# EZEDA_OpenLightingController.net
KiCad netlist of a schematic drawn in EasyEDA Pro
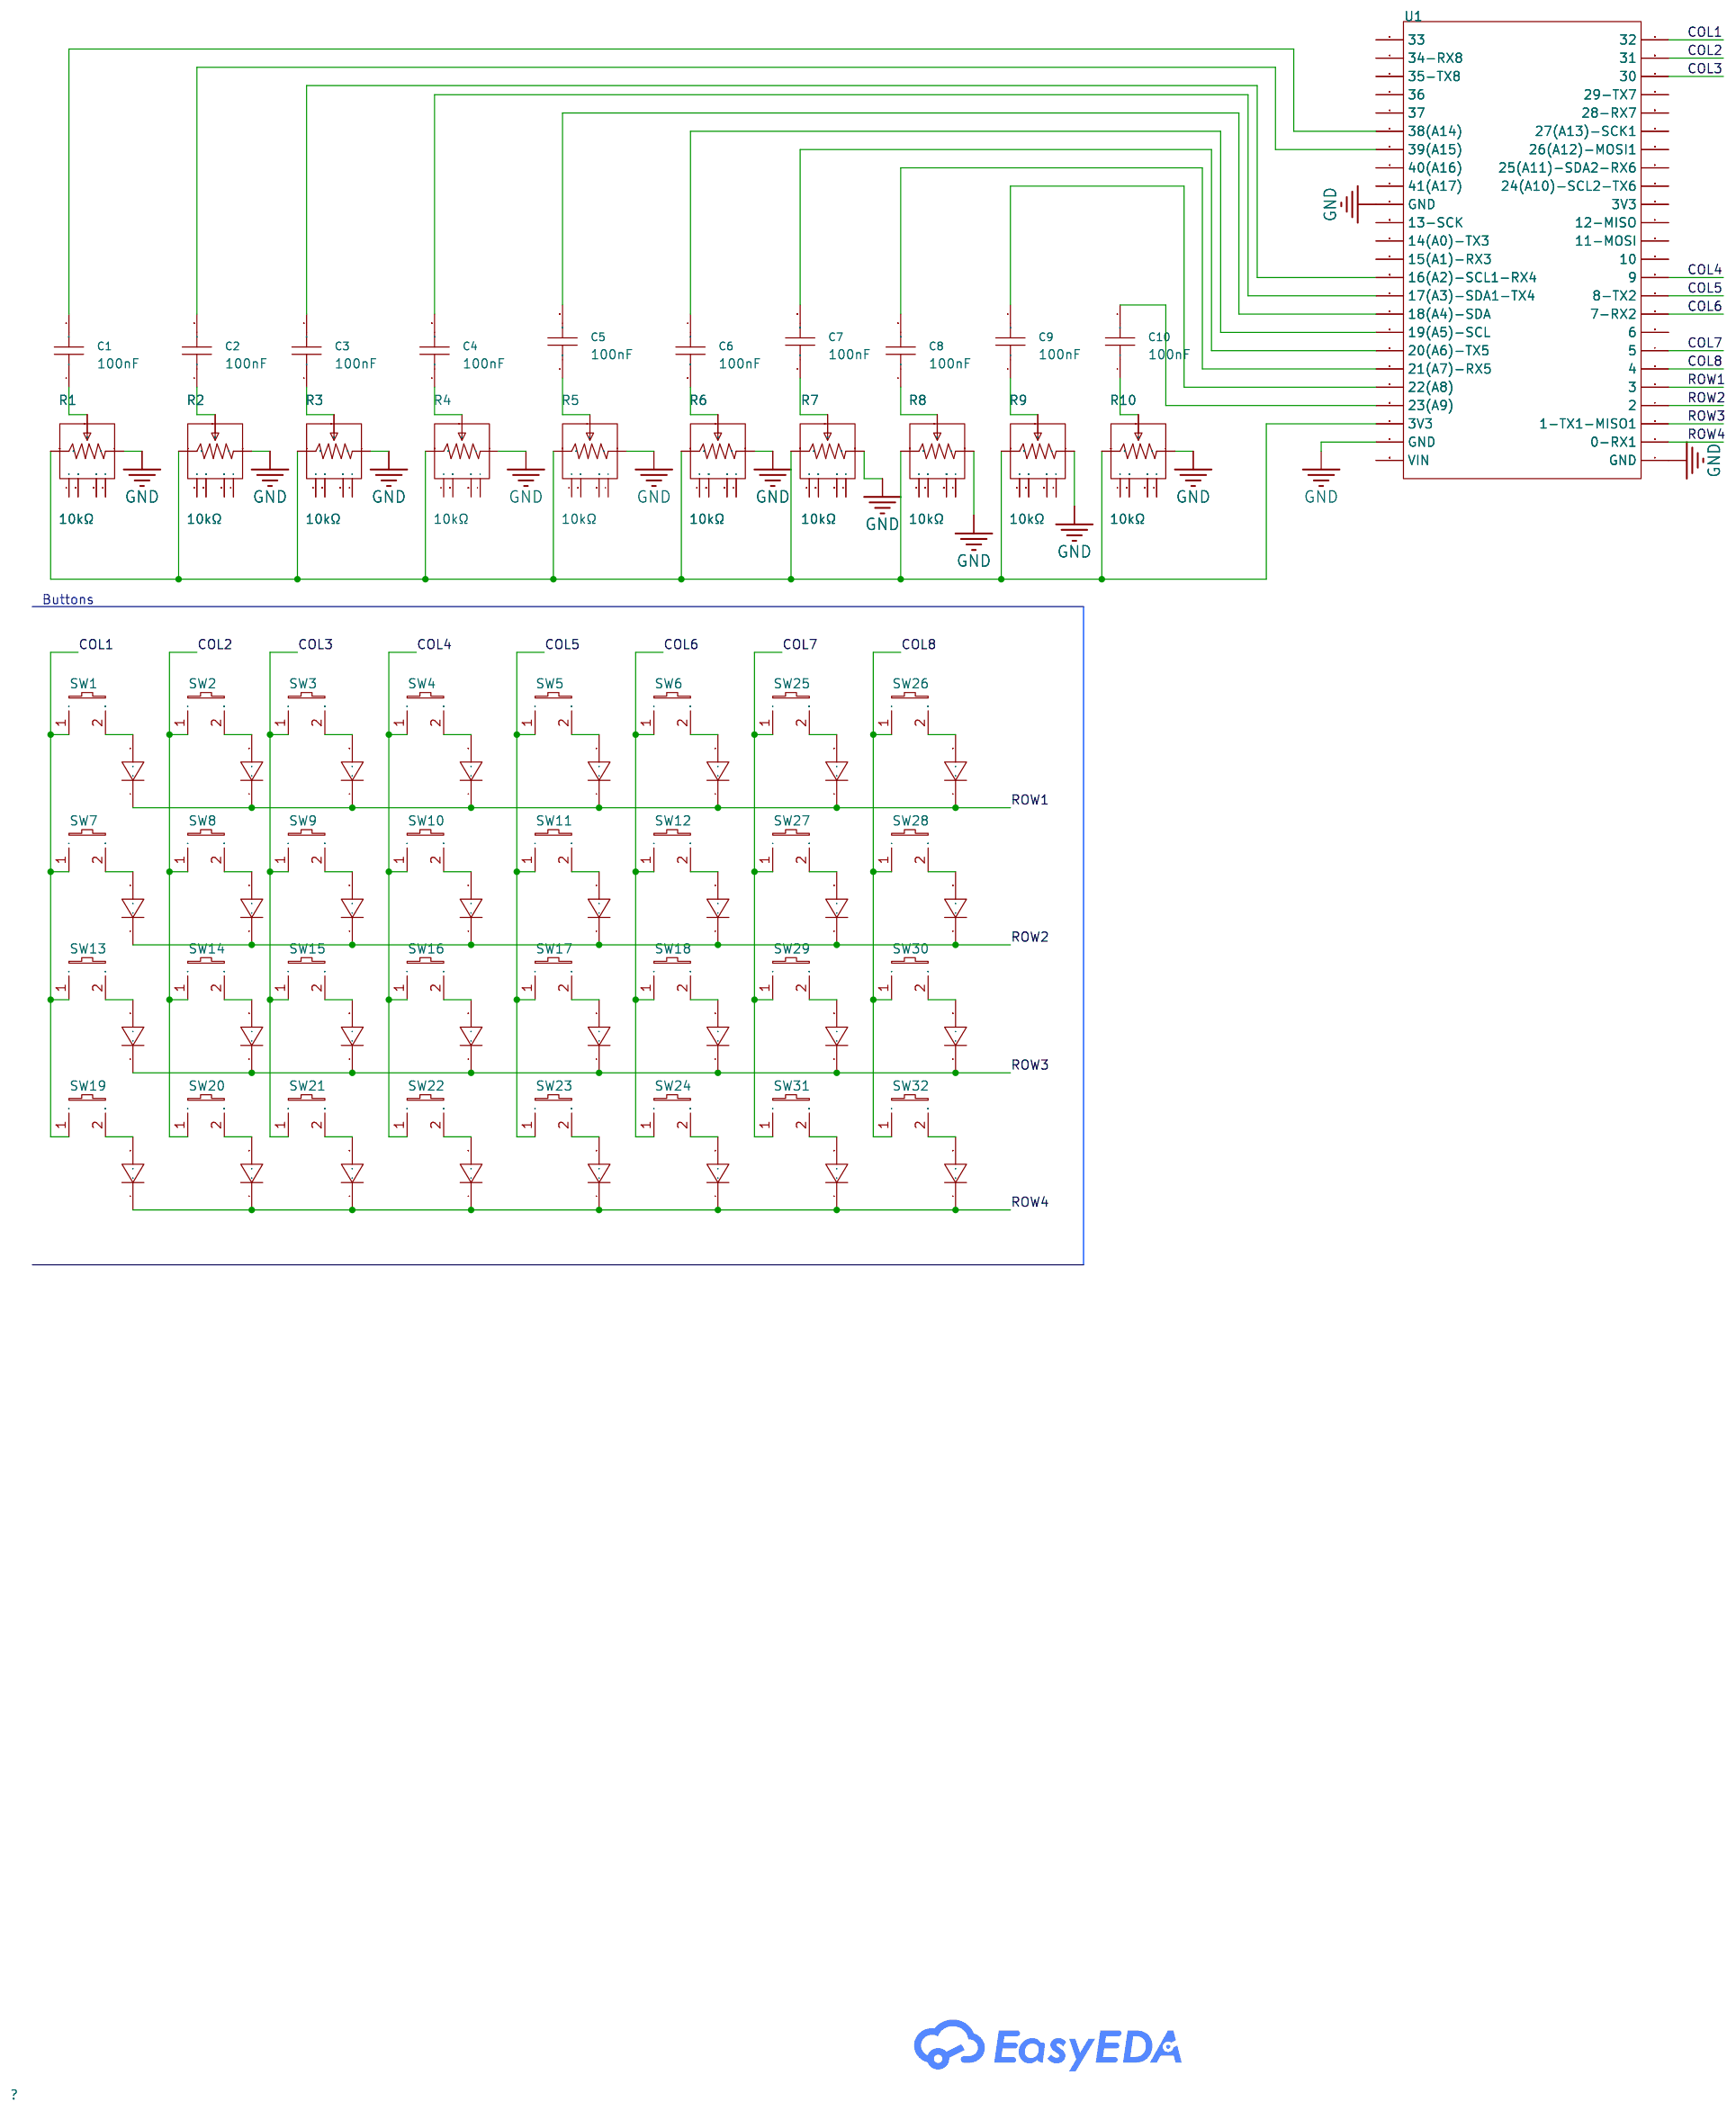
[diagram p0: schematic sheet]

(export (version "E")
  (design (tool "Eeschema 10.0.6"))
  (components
    (comp (ref "C1")
      (value "100nF")
      (footprint "easyedapro:C0603")
      (fields
        (field (name "Manufacturer Part") "CC1H104ZA1ED3F5P1100")
        (field (name "Manufacturer") "Dersonic(德尔创)")
      )
      (libsource (lib "easyedapro") (part "CL10B104KB8NNNC"))
    )
    (comp (ref "C2")
      (value "100nF")
      (footprint "easyedapro:C0603")
      (fields
        (field (name "Manufacturer Part") "CC1H104ZA1ED3F5P1100")
        (field (name "Manufacturer") "Dersonic(德尔创)")
      )
      (libsource (lib "easyedapro") (part "CL10B104KB8NNNC"))
    )
    (comp (ref "C3")
      (value "100nF")
      (footprint "easyedapro:C0603")
      (fields
        (field (name "Manufacturer Part") "CC1H104ZA1ED3F5P1100")
        (field (name "Manufacturer") "Dersonic(德尔创)")
      )
      (libsource (lib "easyedapro") (part "CL10B104KB8NNNC"))
    )
    (comp (ref "C4")
      (value "100nF")
      (footprint "easyedapro:C0603")
      (fields
        (field (name "Manufacturer Part") "CC1H104ZA1ED3F5P1100")
        (field (name "Manufacturer") "Dersonic(德尔创)")
      )
      (libsource (lib "easyedapro") (part "CL10B104KB8NNNC"))
    )
    (comp (ref "C5")
      (value "100nF")
      (footprint "easyedapro:C0603")
      (fields
        (field (name "Manufacturer Part") "CC1H104ZA1ED3F5P1100")
        (field (name "Manufacturer") "Dersonic(德尔创)")
      )
      (libsource (lib "easyedapro") (part "CL10B104KB8NNNC"))
    )
    (comp (ref "C6")
      (value "100nF")
      (footprint "easyedapro:C0603")
      (fields
        (field (name "Manufacturer Part") "CC1H104ZA1ED3F5P1100")
        (field (name "Manufacturer") "Dersonic(德尔创)")
      )
      (libsource (lib "easyedapro") (part "CL10B104KB8NNNC"))
    )
    (comp (ref "C7")
      (value "100nF")
      (footprint "easyedapro:C0603")
      (fields
        (field (name "Manufacturer Part") "CC1H104ZA1ED3F5P1100")
        (field (name "Manufacturer") "Dersonic(德尔创)")
      )
      (libsource (lib "easyedapro") (part "CL10B104KB8NNNC"))
    )
    (comp (ref "C8")
      (value "100nF")
      (footprint "easyedapro:C0603")
      (fields
        (field (name "Manufacturer Part") "CC1H104ZA1ED3F5P1100")
        (field (name "Manufacturer") "Dersonic(德尔创)")
      )
      (libsource (lib "easyedapro") (part "CL10B104KB8NNNC"))
    )
    (comp (ref "C9")
      (value "100nF")
      (footprint "easyedapro:C0603")
      (fields
        (field (name "Manufacturer Part") "CC1H104ZA1ED3F5P1100")
        (field (name "Manufacturer") "Dersonic(德尔创)")
      )
      (libsource (lib "easyedapro") (part "CL10B104KB8NNNC"))
    )
    (comp (ref "C10")
      (value "100nF")
      (footprint "easyedapro:C0603")
      (fields
        (field (name "Manufacturer Part") "CC1H104ZA1ED3F5P1100")
        (field (name "Manufacturer") "Dersonic(德尔创)")
      )
      (libsource (lib "easyedapro") (part "CL10B104KB8NNNC"))
    )
    (comp (ref "D1")
      (value "1N4148")
      (footprint "easyedapro:SOD-123F_L2.7-W1.6-LS3.8-RD")
      (fields (field (name "Manufacturer") "onsemi(安森美)"))
      (libsource (lib "easyedapro") (part "1N4148W_C81598"))
    )
    (comp (ref "D2")
      (value "1N4148")
      (footprint "easyedapro:SOD-123F_L2.7-W1.6-LS3.8-RD")
      (fields (field (name "Manufacturer") "onsemi(安森美)"))
      (libsource (lib "easyedapro") (part "1N4148W_C81598"))
    )
    (comp (ref "D3")
      (value "1N4148")
      (footprint "easyedapro:SOD-123F_L2.7-W1.6-LS3.8-RD")
      (fields (field (name "Manufacturer") "onsemi(安森美)"))
      (libsource (lib "easyedapro") (part "1N4148W_C81598"))
    )
    (comp (ref "D4")
      (value "1N4148")
      (footprint "easyedapro:SOD-123F_L2.7-W1.6-LS3.8-RD")
      (fields (field (name "Manufacturer") "onsemi(安森美)"))
      (libsource (lib "easyedapro") (part "1N4148W_C81598"))
    )
    (comp (ref "D5")
      (value "1N4148")
      (footprint "easyedapro:SOD-123F_L2.7-W1.6-LS3.8-RD")
      (fields (field (name "Manufacturer") "onsemi(安森美)"))
      (libsource (lib "easyedapro") (part "1N4148W_C81598"))
    )
    (comp (ref "D6")
      (value "1N4148")
      (footprint "easyedapro:SOD-123F_L2.7-W1.6-LS3.8-RD")
      (fields (field (name "Manufacturer") "onsemi(安森美)"))
      (libsource (lib "easyedapro") (part "1N4148W_C81598"))
    )
    (comp (ref "D7")
      (value "1N4148")
      (footprint "easyedapro:SOD-123F_L2.7-W1.6-LS3.8-RD")
      (fields (field (name "Manufacturer") "onsemi(安森美)"))
      (libsource (lib "easyedapro") (part "1N4148W_C81598"))
    )
    (comp (ref "D8")
      (value "1N4148")
      (footprint "easyedapro:SOD-123F_L2.7-W1.6-LS3.8-RD")
      (fields (field (name "Manufacturer") "onsemi(安森美)"))
      (libsource (lib "easyedapro") (part "1N4148W_C81598"))
    )
    (comp (ref "D9")
      (value "1N4148")
      (footprint "easyedapro:SOD-123F_L2.7-W1.6-LS3.8-RD")
      (fields (field (name "Manufacturer") "onsemi(安森美)"))
      (libsource (lib "easyedapro") (part "1N4148W_C81598"))
    )
    (comp (ref "D10")
      (value "1N4148")
      (footprint "easyedapro:SOD-123F_L2.7-W1.6-LS3.8-RD")
      (fields (field (name "Manufacturer") "onsemi(安森美)"))
      (libsource (lib "easyedapro") (part "1N4148W_C81598"))
    )
    (comp (ref "D11")
      (value "1N4148")
      (footprint "easyedapro:SOD-123F_L2.7-W1.6-LS3.8-RD")
      (fields (field (name "Manufacturer") "onsemi(安森美)"))
      (libsource (lib "easyedapro") (part "1N4148W_C81598"))
    )
    (comp (ref "D12")
      (value "1N4148")
      (footprint "easyedapro:SOD-123F_L2.7-W1.6-LS3.8-RD")
      (fields (field (name "Manufacturer") "onsemi(安森美)"))
      (libsource (lib "easyedapro") (part "1N4148W_C81598"))
    )
    (comp (ref "D13")
      (value "1N4148")
      (footprint "easyedapro:SOD-123F_L2.7-W1.6-LS3.8-RD")
      (fields (field (name "Manufacturer") "onsemi(安森美)"))
      (libsource (lib "easyedapro") (part "1N4148W_C81598"))
    )
    (comp (ref "D14")
      (value "1N4148")
      (footprint "easyedapro:SOD-123F_L2.7-W1.6-LS3.8-RD")
      (fields (field (name "Manufacturer") "onsemi(安森美)"))
      (libsource (lib "easyedapro") (part "1N4148W_C81598"))
    )
    (comp (ref "D15")
      (value "1N4148")
      (footprint "easyedapro:SOD-123F_L2.7-W1.6-LS3.8-RD")
      (fields (field (name "Manufacturer") "onsemi(安森美)"))
      (libsource (lib "easyedapro") (part "1N4148W_C81598"))
    )
    (comp (ref "D16")
      (value "1N4148")
      (footprint "easyedapro:SOD-123F_L2.7-W1.6-LS3.8-RD")
      (fields (field (name "Manufacturer") "onsemi(安森美)"))
      (libsource (lib "easyedapro") (part "1N4148W_C81598"))
    )
    (comp (ref "D17")
      (value "1N4148")
      (footprint "easyedapro:SOD-123F_L2.7-W1.6-LS3.8-RD")
      (fields (field (name "Manufacturer") "onsemi(安森美)"))
      (libsource (lib "easyedapro") (part "1N4148W_C81598"))
    )
    (comp (ref "D18")
      (value "1N4148")
      (footprint "easyedapro:SOD-123F_L2.7-W1.6-LS3.8-RD")
      (fields (field (name "Manufacturer") "onsemi(安森美)"))
      (libsource (lib "easyedapro") (part "1N4148W_C81598"))
    )
    (comp (ref "D19")
      (value "1N4148")
      (footprint "easyedapro:SOD-123F_L2.7-W1.6-LS3.8-RD")
      (fields (field (name "Manufacturer") "onsemi(安森美)"))
      (libsource (lib "easyedapro") (part "1N4148W_C81598"))
    )
    (comp (ref "D20")
      (value "1N4148")
      (footprint "easyedapro:SOD-123F_L2.7-W1.6-LS3.8-RD")
      (fields (field (name "Manufacturer") "onsemi(安森美)"))
      (libsource (lib "easyedapro") (part "1N4148W_C81598"))
    )
    (comp (ref "D21")
      (value "1N4148")
      (footprint "easyedapro:SOD-123F_L2.7-W1.6-LS3.8-RD")
      (fields (field (name "Manufacturer") "onsemi(安森美)"))
      (libsource (lib "easyedapro") (part "1N4148W_C81598"))
    )
    (comp (ref "D22")
      (value "1N4148")
      (footprint "easyedapro:SOD-123F_L2.7-W1.6-LS3.8-RD")
      (fields (field (name "Manufacturer") "onsemi(安森美)"))
      (libsource (lib "easyedapro") (part "1N4148W_C81598"))
    )
    (comp (ref "D23")
      (value "1N4148")
      (footprint "easyedapro:SOD-123F_L2.7-W1.6-LS3.8-RD")
      (fields (field (name "Manufacturer") "onsemi(安森美)"))
      (libsource (lib "easyedapro") (part "1N4148W_C81598"))
    )
    (comp (ref "D24")
      (value "1N4148")
      (footprint "easyedapro:SOD-123F_L2.7-W1.6-LS3.8-RD")
      (fields (field (name "Manufacturer") "onsemi(安森美)"))
      (libsource (lib "easyedapro") (part "1N4148W_C81598"))
    )
    (comp (ref "D25")
      (value "1N4148")
      (footprint "easyedapro:SOD-123F_L2.7-W1.6-LS3.8-RD")
      (fields (field (name "Manufacturer") "onsemi(安森美)"))
      (libsource (lib "easyedapro") (part "1N4148W_C81598"))
    )
    (comp (ref "D26")
      (value "1N4148")
      (footprint "easyedapro:SOD-123F_L2.7-W1.6-LS3.8-RD")
      (fields (field (name "Manufacturer") "onsemi(安森美)"))
      (libsource (lib "easyedapro") (part "1N4148W_C81598"))
    )
    (comp (ref "D27")
      (value "1N4148")
      (footprint "easyedapro:SOD-123F_L2.7-W1.6-LS3.8-RD")
      (fields (field (name "Manufacturer") "onsemi(安森美)"))
      (libsource (lib "easyedapro") (part "1N4148W_C81598"))
    )
    (comp (ref "D28")
      (value "1N4148")
      (footprint "easyedapro:SOD-123F_L2.7-W1.6-LS3.8-RD")
      (fields (field (name "Manufacturer") "onsemi(安森美)"))
      (libsource (lib "easyedapro") (part "1N4148W_C81598"))
    )
    (comp (ref "D29")
      (value "1N4148")
      (footprint "easyedapro:SOD-123F_L2.7-W1.6-LS3.8-RD")
      (fields (field (name "Manufacturer") "onsemi(安森美)"))
      (libsource (lib "easyedapro") (part "1N4148W_C81598"))
    )
    (comp (ref "D30")
      (value "1N4148")
      (footprint "easyedapro:SOD-123F_L2.7-W1.6-LS3.8-RD")
      (fields (field (name "Manufacturer") "onsemi(安森美)"))
      (libsource (lib "easyedapro") (part "1N4148W_C81598"))
    )
    (comp (ref "D31")
      (value "1N4148")
      (footprint "easyedapro:SOD-123F_L2.7-W1.6-LS3.8-RD")
      (fields (field (name "Manufacturer") "onsemi(安森美)"))
      (libsource (lib "easyedapro") (part "1N4148W_C81598"))
    )
    (comp (ref "D32")
      (value "1N4148")
      (footprint "easyedapro:SOD-123F_L2.7-W1.6-LS3.8-RD")
      (fields (field (name "Manufacturer") "onsemi(安森美)"))
      (libsource (lib "easyedapro") (part "1N4148W_C81598"))
    )
    (comp (ref "R1")
      (value "10kΩ")
      (footprint "easyedapro:RES-ADJ-TH_PTA6043-2015DPB103")
      (description "Resistance:10kΩ Tolerance:±20% Tolerance:±20% Voltage Rating:200V Power(Watts):250mW")
      (fields (field (name "Manufacturer Part") "PTA6043-2015CPB103") (field (name "Manufacturer") "BOURNS"))
      (libsource (lib "easyedapro") (part "PTA6043-2015CPB103"))
    )
    (comp (ref "R2")
      (value "10kΩ")
      (footprint "easyedapro:RES-ADJ-TH_PTA6043-2015DPB103")
      (description "Resistance:10kΩ Tolerance:±20% Tolerance:±20% Voltage Rating:200V Power(Watts):250mW")
      (fields (field (name "Manufacturer Part") "PTA6043-2015CPB103") (field (name "Manufacturer") "BOURNS"))
      (libsource (lib "easyedapro") (part "PTA6043-2015CPB103"))
    )
    (comp (ref "R3")
      (value "10kΩ")
      (footprint "easyedapro:RES-ADJ-TH_PTA6043-2015DPB103")
      (description "Resistance:10kΩ Tolerance:±20% Tolerance:±20% Voltage Rating:200V Power(Watts):250mW")
      (fields (field (name "Manufacturer Part") "PTA6043-2015CPB103") (field (name "Manufacturer") "BOURNS"))
      (libsource (lib "easyedapro") (part "PTA6043-2015CPB103"))
    )
    (comp (ref "R4")
      (value "10kΩ")
      (footprint "easyedapro:RES-ADJ-TH_PTA6043-2015DPB103")
      (description "Resistance:10kΩ Tolerance:±20% Tolerance:±20% Voltage Rating:200V Power(Watts):250mW")
      (fields (field (name "Manufacturer Part") "PTA6043-2015CPB103") (field (name "Manufacturer") "BOURNS"))
      (libsource (lib "easyedapro") (part "PTA6043-2015CPB103"))
    )
    (comp (ref "R5")
      (value "10kΩ")
      (footprint "easyedapro:RES-ADJ-TH_PTA6043-2015DPB103")
      (description "Resistance:10kΩ Tolerance:±20% Tolerance:±20% Voltage Rating:200V Power(Watts):250mW")
      (fields (field (name "Manufacturer Part") "PTA6043-2015CPB103") (field (name "Manufacturer") "BOURNS"))
      (libsource (lib "easyedapro") (part "PTA6043-2015CPB103"))
    )
    (comp (ref "R6")
      (value "10kΩ")
      (footprint "easyedapro:RES-ADJ-TH_PTA6043-2015DPB103")
      (description "Resistance:10kΩ Tolerance:±20% Tolerance:±20% Voltage Rating:200V Power(Watts):250mW")
      (fields (field (name "Manufacturer Part") "PTA6043-2015CPB103") (field (name "Manufacturer") "BOURNS"))
      (libsource (lib "easyedapro") (part "PTA6043-2015CPB103"))
    )
    (comp (ref "R7")
      (value "10kΩ")
      (footprint "easyedapro:RES-ADJ-TH_PTA6043-2015DPB103")
      (description "Resistance:10kΩ Tolerance:±20% Tolerance:±20% Voltage Rating:200V Power(Watts):250mW")
      (fields (field (name "Manufacturer Part") "PTA6043-2015CPB103") (field (name "Manufacturer") "BOURNS"))
      (libsource (lib "easyedapro") (part "PTA6043-2015CPB103"))
    )
    (comp (ref "R8")
      (value "10kΩ")
      (footprint "easyedapro:RES-ADJ-TH_PTA6043-2015DPB103")
      (description "Resistance:10kΩ Tolerance:±20% Tolerance:±20% Voltage Rating:200V Power(Watts):250mW")
      (fields (field (name "Manufacturer Part") "PTA6043-2015CPB103") (field (name "Manufacturer") "BOURNS"))
      (libsource (lib "easyedapro") (part "PTA6043-2015CPB103"))
    )
    (comp (ref "R9")
      (value "10kΩ")
      (footprint "easyedapro:RES-ADJ-TH_PTA6043-2015DPB103")
      (description "Resistance:10kΩ Tolerance:±20% Tolerance:±20% Voltage Rating:200V Power(Watts):250mW")
      (fields (field (name "Manufacturer Part") "PTA6043-2015CPB103") (field (name "Manufacturer") "BOURNS"))
      (libsource (lib "easyedapro") (part "PTA6043-2015CPB103"))
    )
    (comp (ref "R10")
      (value "10kΩ")
      (footprint "easyedapro:RES-ADJ-TH_PTA6043-2015DPB103")
      (description "Resistance:10kΩ Tolerance:±20% Tolerance:±20% Voltage Rating:200V Power(Watts):250mW")
      (fields (field (name "Manufacturer Part") "PTA6043-2015CPB103") (field (name "Manufacturer") "BOURNS"))
      (libsource (lib "easyedapro") (part "PTA6043-2015CPB103"))
    )
    (comp (ref "SW1")
      (value "MX Switch")
      (footprint "easyedapro:SW-TH_MX1A-11NW")
      (fields (field (name "Manufacturer Part") "MX1A-11NW") (field (name "Manufacturer") "CHERRY"))
      (libsource (lib "easyedapro") (part "MX1A-11NW"))
    )
    (comp (ref "SW2")
      (value "MX Switch")
      (footprint "easyedapro:SW-TH_MX1A-11NW")
      (fields (field (name "Manufacturer Part") "MX1A-11NW") (field (name "Manufacturer") "CHERRY"))
      (libsource (lib "easyedapro") (part "MX1A-11NW"))
    )
    (comp (ref "SW3")
      (value "MX Switch")
      (footprint "easyedapro:SW-TH_MX1A-11NW")
      (fields (field (name "Manufacturer Part") "MX1A-11NW") (field (name "Manufacturer") "CHERRY"))
      (libsource (lib "easyedapro") (part "MX1A-11NW"))
    )
    (comp (ref "SW4")
      (value "MX Switch")
      (footprint "easyedapro:SW-TH_MX1A-11NW")
      (fields (field (name "Manufacturer Part") "MX1A-11NW") (field (name "Manufacturer") "CHERRY"))
      (libsource (lib "easyedapro") (part "MX1A-11NW"))
    )
    (comp (ref "SW5")
      (value "MX Switch")
      (footprint "easyedapro:SW-TH_MX1A-11NW")
      (fields (field (name "Manufacturer Part") "MX1A-11NW") (field (name "Manufacturer") "CHERRY"))
      (libsource (lib "easyedapro") (part "MX1A-11NW"))
    )
    (comp (ref "SW6")
      (value "MX Switch")
      (footprint "easyedapro:SW-TH_MX1A-11NW")
      (fields (field (name "Manufacturer Part") "MX1A-11NW") (field (name "Manufacturer") "CHERRY"))
      (libsource (lib "easyedapro") (part "MX1A-11NW"))
    )
    (comp (ref "SW7")
      (value "MX Switch")
      (footprint "easyedapro:SW-TH_MX1A-11NW")
      (fields (field (name "Manufacturer Part") "MX1A-11NW") (field (name "Manufacturer") "CHERRY"))
      (libsource (lib "easyedapro") (part "MX1A-11NW"))
    )
    (comp (ref "SW8")
      (value "MX Switch")
      (footprint "easyedapro:SW-TH_MX1A-11NW")
      (fields (field (name "Manufacturer Part") "MX1A-11NW") (field (name "Manufacturer") "CHERRY"))
      (libsource (lib "easyedapro") (part "MX1A-11NW"))
    )
    (comp (ref "SW9")
      (value "MX Switch")
      (footprint "easyedapro:SW-TH_MX1A-11NW")
      (fields (field (name "Manufacturer Part") "MX1A-11NW") (field (name "Manufacturer") "CHERRY"))
      (libsource (lib "easyedapro") (part "MX1A-11NW"))
    )
    (comp (ref "SW10")
      (value "MX Switch")
      (footprint "easyedapro:SW-TH_MX1A-11NW")
      (fields (field (name "Manufacturer Part") "MX1A-11NW") (field (name "Manufacturer") "CHERRY"))
      (libsource (lib "easyedapro") (part "MX1A-11NW"))
    )
    (comp (ref "SW11")
      (value "MX Switch")
      (footprint "easyedapro:SW-TH_MX1A-11NW")
      (fields (field (name "Manufacturer Part") "MX1A-11NW") (field (name "Manufacturer") "CHERRY"))
      (libsource (lib "easyedapro") (part "MX1A-11NW"))
    )
    (comp (ref "SW12")
      (value "MX Switch")
      (footprint "easyedapro:SW-TH_MX1A-11NW")
      (fields (field (name "Manufacturer Part") "MX1A-11NW") (field (name "Manufacturer") "CHERRY"))
      (libsource (lib "easyedapro") (part "MX1A-11NW"))
    )
    (comp (ref "SW13")
      (value "MX Switch")
      (footprint "easyedapro:SW-TH_MX1A-11NW")
      (fields (field (name "Manufacturer Part") "MX1A-11NW") (field (name "Manufacturer") "CHERRY"))
      (libsource (lib "easyedapro") (part "MX1A-11NW"))
    )
    (comp (ref "SW14")
      (value "MX Switch")
      (footprint "easyedapro:SW-TH_MX1A-11NW")
      (fields (field (name "Manufacturer Part") "MX1A-11NW") (field (name "Manufacturer") "CHERRY"))
      (libsource (lib "easyedapro") (part "MX1A-11NW"))
    )
    (comp (ref "SW15")
      (value "MX Switch")
      (footprint "easyedapro:SW-TH_MX1A-11NW")
      (fields (field (name "Manufacturer Part") "MX1A-11NW") (field (name "Manufacturer") "CHERRY"))
      (libsource (lib "easyedapro") (part "MX1A-11NW"))
    )
    (comp (ref "SW16")
      (value "MX Switch")
      (footprint "easyedapro:SW-TH_MX1A-11NW")
      (fields (field (name "Manufacturer Part") "MX1A-11NW") (field (name "Manufacturer") "CHERRY"))
      (libsource (lib "easyedapro") (part "MX1A-11NW"))
    )
    (comp (ref "SW17")
      (value "MX Switch")
      (footprint "easyedapro:SW-TH_MX1A-11NW")
      (fields (field (name "Manufacturer Part") "MX1A-11NW") (field (name "Manufacturer") "CHERRY"))
      (libsource (lib "easyedapro") (part "MX1A-11NW"))
    )
    (comp (ref "SW18")
      (value "MX Switch")
      (footprint "easyedapro:SW-TH_MX1A-11NW")
      (fields (field (name "Manufacturer Part") "MX1A-11NW") (field (name "Manufacturer") "CHERRY"))
      (libsource (lib "easyedapro") (part "MX1A-11NW"))
    )
    (comp (ref "SW19")
      (value "MX Switch")
      (footprint "easyedapro:SW-TH_MX1A-11NW")
      (fields (field (name "Manufacturer Part") "MX1A-11NW") (field (name "Manufacturer") "CHERRY"))
      (libsource (lib "easyedapro") (part "MX1A-11NW"))
    )
    (comp (ref "SW20")
      (value "MX Switch")
      (footprint "easyedapro:SW-TH_MX1A-11NW")
      (fields (field (name "Manufacturer Part") "MX1A-11NW") (field (name "Manufacturer") "CHERRY"))
      (libsource (lib "easyedapro") (part "MX1A-11NW"))
    )
    (comp (ref "SW21")
      (value "MX Switch")
      (footprint "easyedapro:SW-TH_MX1A-11NW")
      (fields (field (name "Manufacturer Part") "MX1A-11NW") (field (name "Manufacturer") "CHERRY"))
      (libsource (lib "easyedapro") (part "MX1A-11NW"))
    )
    (comp (ref "SW22")
      (value "MX Switch")
      (footprint "easyedapro:SW-TH_MX1A-11NW")
      (fields (field (name "Manufacturer Part") "MX1A-11NW") (field (name "Manufacturer") "CHERRY"))
      (libsource (lib "easyedapro") (part "MX1A-11NW"))
    )
    (comp (ref "SW23")
      (value "MX Switch")
      (footprint "easyedapro:SW-TH_MX1A-11NW")
      (fields (field (name "Manufacturer Part") "MX1A-11NW") (field (name "Manufacturer") "CHERRY"))
      (libsource (lib "easyedapro") (part "MX1A-11NW"))
    )
    (comp (ref "SW24")
      (value "MX Switch")
      (footprint "easyedapro:SW-TH_MX1A-11NW")
      (fields (field (name "Manufacturer Part") "MX1A-11NW") (field (name "Manufacturer") "CHERRY"))
      (libsource (lib "easyedapro") (part "MX1A-11NW"))
    )
    (comp (ref "SW25")
      (value "MX Switch")
      (footprint "easyedapro:SW-TH_MX1A-11NW")
      (fields (field (name "Manufacturer Part") "MX1A-11NW") (field (name "Manufacturer") "CHERRY"))
      (libsource (lib "easyedapro") (part "MX1A-11NW"))
    )
    (comp (ref "SW26")
      (value "MX Switch")
      (footprint "easyedapro:SW-TH_MX1A-11NW")
      (fields (field (name "Manufacturer Part") "MX1A-11NW") (field (name "Manufacturer") "CHERRY"))
      (libsource (lib "easyedapro") (part "MX1A-11NW"))
    )
    (comp (ref "SW27")
      (value "MX Switch")
      (footprint "easyedapro:SW-TH_MX1A-11NW")
      (fields (field (name "Manufacturer Part") "MX1A-11NW") (field (name "Manufacturer") "CHERRY"))
      (libsource (lib "easyedapro") (part "MX1A-11NW"))
    )
    (comp (ref "SW28")
      (value "MX Switch")
      (footprint "easyedapro:SW-TH_MX1A-11NW")
      (fields (field (name "Manufacturer Part") "MX1A-11NW") (field (name "Manufacturer") "CHERRY"))
      (libsource (lib "easyedapro") (part "MX1A-11NW"))
    )
    (comp (ref "SW29")
      (value "MX Switch")
      (footprint "easyedapro:SW-TH_MX1A-11NW")
      (fields (field (name "Manufacturer Part") "MX1A-11NW") (field (name "Manufacturer") "CHERRY"))
      (libsource (lib "easyedapro") (part "MX1A-11NW"))
    )
    (comp (ref "SW30")
      (value "MX Switch")
      (footprint "easyedapro:SW-TH_MX1A-11NW")
      (fields (field (name "Manufacturer Part") "MX1A-11NW") (field (name "Manufacturer") "CHERRY"))
      (libsource (lib "easyedapro") (part "MX1A-11NW"))
    )
    (comp (ref "SW31")
      (value "MX Switch")
      (footprint "easyedapro:SW-TH_MX1A-11NW")
      (fields (field (name "Manufacturer Part") "MX1A-11NW") (field (name "Manufacturer") "CHERRY"))
      (libsource (lib "easyedapro") (part "MX1A-11NW"))
    )
    (comp (ref "SW32")
      (value "MX Switch")
      (footprint "easyedapro:SW-TH_MX1A-11NW")
      (fields (field (name "Manufacturer Part") "MX1A-11NW") (field (name "Manufacturer") "CHERRY"))
      (libsource (lib "easyedapro") (part "MX1A-11NW"))
    )
    (comp (ref "U1")
      (value "~")
      (footprint "easyedapro:teensy 4.1")
      (libsource (lib "easyedapro") (part "teensy 4.1"))
    )
  )
  (nets
    (net (code "1") (name "/COL1") (class "Default")
      (node (ref "SW1") (pin "1") (pinfunction "1_1") (pintype "unspecified"))
      (node (ref "SW13") (pin "1") (pinfunction "1_1") (pintype "unspecified"))
      (node (ref "SW19") (pin "1") (pinfunction "1_1") (pintype "unspecified"))
      (node (ref "SW7") (pin "1") (pinfunction "1_1") (pintype "unspecified"))
      (node (ref "U1") (pin "24") (pinfunction "32_24") (pintype "input"))
    )
    (net (code "2") (name "/COL2") (class "Default")
      (node (ref "SW14") (pin "1") (pinfunction "1_1") (pintype "unspecified"))
      (node (ref "SW2") (pin "1") (pinfunction "1_1") (pintype "unspecified"))
      (node (ref "SW20") (pin "1") (pinfunction "1_1") (pintype "unspecified"))
      (node (ref "SW8") (pin "1") (pinfunction "1_1") (pintype "unspecified"))
      (node (ref "U1") (pin "23") (pinfunction "31_23") (pintype "input"))
    )
    (net (code "3") (name "/COL3") (class "Default")
      (node (ref "SW15") (pin "1") (pinfunction "1_1") (pintype "unspecified"))
      (node (ref "SW21") (pin "1") (pinfunction "1_1") (pintype "unspecified"))
      (node (ref "SW3") (pin "1") (pinfunction "1_1") (pintype "unspecified"))
      (node (ref "SW9") (pin "1") (pinfunction "1_1") (pintype "unspecified"))
      (node (ref "U1") (pin "22") (pinfunction "30_22") (pintype "input"))
    )
    (net (code "4") (name "/COL4") (class "Default")
      (node (ref "SW10") (pin "1") (pinfunction "1_1") (pintype "unspecified"))
      (node (ref "SW16") (pin "1") (pinfunction "1_1") (pintype "unspecified"))
      (node (ref "SW22") (pin "1") (pinfunction "1_1") (pintype "unspecified"))
      (node (ref "SW4") (pin "1") (pinfunction "1_1") (pintype "unspecified"))
      (node (ref "U1") (pin "11") (pinfunction "9_11") (pintype "input"))
    )
    (net (code "5") (name "/COL5") (class "Default")
      (node (ref "SW11") (pin "1") (pinfunction "1_1") (pintype "unspecified"))
      (node (ref "SW17") (pin "1") (pinfunction "1_1") (pintype "unspecified"))
      (node (ref "SW23") (pin "1") (pinfunction "1_1") (pintype "unspecified"))
      (node (ref "SW5") (pin "1") (pinfunction "1_1") (pintype "unspecified"))
      (node (ref "U1") (pin "10") (pinfunction "8-TX2_10") (pintype "input"))
    )
    (net (code "6") (name "/COL6") (class "Default")
      (node (ref "SW12") (pin "1") (pinfunction "1_1") (pintype "unspecified"))
      (node (ref "SW18") (pin "1") (pinfunction "1_1") (pintype "unspecified"))
      (node (ref "SW24") (pin "1") (pinfunction "1_1") (pintype "unspecified"))
      (node (ref "SW6") (pin "1") (pinfunction "1_1") (pintype "unspecified"))
      (node (ref "U1") (pin "9") (pinfunction "7-RX2_9") (pintype "input"))
    )
    (net (code "7") (name "/COL7") (class "Default")
      (node (ref "SW25") (pin "1") (pinfunction "1_1") (pintype "unspecified"))
      (node (ref "SW27") (pin "1") (pinfunction "1_1") (pintype "unspecified"))
      (node (ref "SW29") (pin "1") (pinfunction "1_1") (pintype "unspecified"))
      (node (ref "SW31") (pin "1") (pinfunction "1_1") (pintype "unspecified"))
      (node (ref "U1") (pin "7") (pinfunction "5_7") (pintype "input"))
    )
    (net (code "8") (name "/COL8") (class "Default")
      (node (ref "SW26") (pin "1") (pinfunction "1_1") (pintype "unspecified"))
      (node (ref "SW28") (pin "1") (pinfunction "1_1") (pintype "unspecified"))
      (node (ref "SW30") (pin "1") (pinfunction "1_1") (pintype "unspecified"))
      (node (ref "SW32") (pin "1") (pinfunction "1_1") (pintype "unspecified"))
      (node (ref "U1") (pin "6") (pinfunction "4_6") (pintype "input"))
    )
    (net (code "9") (name "/ROW1") (class "Default")
      (node (ref "D1") (pin "1") (pinfunction "K_1") (pintype "unspecified"))
      (node (ref "D2") (pin "1") (pinfunction "K_1") (pintype "unspecified"))
      (node (ref "D25") (pin "1") (pinfunction "K_1") (pintype "unspecified"))
      (node (ref "D26") (pin "1") (pinfunction "K_1") (pintype "unspecified"))
      (node (ref "D3") (pin "1") (pinfunction "K_1") (pintype "unspecified"))
      (node (ref "D4") (pin "1") (pinfunction "K_1") (pintype "unspecified"))
      (node (ref "D5") (pin "1") (pinfunction "K_1") (pintype "unspecified"))
      (node (ref "D6") (pin "1") (pinfunction "K_1") (pintype "unspecified"))
      (node (ref "U1") (pin "5") (pinfunction "3_5") (pintype "input"))
    )
    (net (code "10") (name "/ROW2") (class "Default")
      (node (ref "D10") (pin "1") (pinfunction "K_1") (pintype "unspecified"))
      (node (ref "D11") (pin "1") (pinfunction "K_1") (pintype "unspecified"))
      (node (ref "D12") (pin "1") (pinfunction "K_1") (pintype "unspecified"))
      (node (ref "D27") (pin "1") (pinfunction "K_1") (pintype "unspecified"))
      (node (ref "D28") (pin "1") (pinfunction "K_1") (pintype "unspecified"))
      (node (ref "D7") (pin "1") (pinfunction "K_1") (pintype "unspecified"))
      (node (ref "D8") (pin "1") (pinfunction "K_1") (pintype "unspecified"))
      (node (ref "D9") (pin "1") (pinfunction "K_1") (pintype "unspecified"))
      (node (ref "U1") (pin "4") (pinfunction "2_4") (pintype "input"))
    )
    (net (code "11") (name "/ROW3") (class "Default")
      (node (ref "D13") (pin "1") (pinfunction "K_1") (pintype "unspecified"))
      (node (ref "D14") (pin "1") (pinfunction "K_1") (pintype "unspecified"))
      (node (ref "D15") (pin "1") (pinfunction "K_1") (pintype "unspecified"))
      (node (ref "D16") (pin "1") (pinfunction "K_1") (pintype "unspecified"))
      (node (ref "D17") (pin "1") (pinfunction "K_1") (pintype "unspecified"))
      (node (ref "D18") (pin "1") (pinfunction "K_1") (pintype "unspecified"))
      (node (ref "D29") (pin "1") (pinfunction "K_1") (pintype "unspecified"))
      (node (ref "D30") (pin "1") (pinfunction "K_1") (pintype "unspecified"))
      (node (ref "U1") (pin "3") (pinfunction "1-TX1-MISO1_3") (pintype "input"))
    )
    (net (code "12") (name "/ROW4") (class "Default")
      (node (ref "D19") (pin "1") (pinfunction "K_1") (pintype "unspecified"))
      (node (ref "D20") (pin "1") (pinfunction "K_1") (pintype "unspecified"))
      (node (ref "D21") (pin "1") (pinfunction "K_1") (pintype "unspecified"))
      (node (ref "D22") (pin "1") (pinfunction "K_1") (pintype "unspecified"))
      (node (ref "D23") (pin "1") (pinfunction "K_1") (pintype "unspecified"))
      (node (ref "D24") (pin "1") (pinfunction "K_1") (pintype "unspecified"))
      (node (ref "D31") (pin "1") (pinfunction "K_1") (pintype "unspecified"))
      (node (ref "D32") (pin "1") (pinfunction "K_1") (pintype "unspecified"))
      (node (ref "U1") (pin "2") (pinfunction "0-RX1_2") (pintype "input"))
    )
    (net (code "13") (name "GND") (class "Default")
      (node (ref "R1") (pin "1") (pinfunction "1_1") (pintype "unspecified"))
      (node (ref "R10") (pin "1") (pinfunction "1_1") (pintype "unspecified"))
      (node (ref "R2") (pin "1") (pinfunction "1_1") (pintype "unspecified"))
      (node (ref "R3") (pin "1") (pinfunction "1_1") (pintype "unspecified"))
      (node (ref "R4") (pin "1") (pinfunction "1_1") (pintype "unspecified"))
      (node (ref "R5") (pin "1") (pinfunction "1_1") (pintype "unspecified"))
      (node (ref "R6") (pin "1") (pinfunction "1_1") (pintype "unspecified"))
      (node (ref "R7") (pin "1") (pinfunction "1_1") (pintype "unspecified"))
      (node (ref "R8") (pin "1") (pinfunction "1_1") (pintype "unspecified"))
      (node (ref "R9") (pin "1") (pinfunction "1_1") (pintype "unspecified"))
      (node (ref "U1") (pin "1") (pinfunction "GND_1") (pintype "input"))
      (node (ref "U1") (pin "26") (pinfunction "GND_26") (pintype "input"))
      (node (ref "U1") (pin "39") (pinfunction "GND_39") (pintype "input"))
    )
    (net (code "14") (name "Net-(C1-Pad1)") (class "Default")
      (node (ref "C1") (pin "1") (pinfunction "1_1") (pintype "input"))
      (node (ref "R1") (pin "2") (pinfunction "2_2") (pintype "unspecified"))
    )
    (net (code "15") (name "Net-(C2-Pad1)") (class "Default")
      (node (ref "C2") (pin "1") (pinfunction "1_1") (pintype "input"))
      (node (ref "R2") (pin "2") (pinfunction "2_2") (pintype "unspecified"))
    )
    (net (code "16") (name "Net-(C3-Pad1)") (class "Default")
      (node (ref "C3") (pin "1") (pinfunction "1_1") (pintype "input"))
      (node (ref "R3") (pin "2") (pinfunction "2_2") (pintype "unspecified"))
    )
    (net (code "17") (name "Net-(C4-Pad1)") (class "Default")
      (node (ref "C4") (pin "1") (pinfunction "1_1") (pintype "input"))
      (node (ref "R4") (pin "2") (pinfunction "2_2") (pintype "unspecified"))
    )
    (net (code "18") (name "Net-(C5-Pad1)") (class "Default")
      (node (ref "C5") (pin "1") (pinfunction "1_1") (pintype "input"))
      (node (ref "R5") (pin "2") (pinfunction "2_2") (pintype "unspecified"))
    )
    (net (code "19") (name "Net-(C6-Pad2)") (class "Default")
      (node (ref "C6") (pin "2") (pinfunction "2_2") (pintype "input"))
      (node (ref "R6") (pin "2") (pinfunction "2_2") (pintype "unspecified"))
    )
    (net (code "20") (name "Net-(C7-Pad1)") (class "Default")
      (node (ref "C7") (pin "1") (pinfunction "1_1") (pintype "input"))
      (node (ref "R7") (pin "2") (pinfunction "2_2") (pintype "unspecified"))
    )
    (net (code "21") (name "Net-(C8-Pad1)") (class "Default")
      (node (ref "C8") (pin "1") (pinfunction "1_1") (pintype "input"))
      (node (ref "R8") (pin "2") (pinfunction "2_2") (pintype "unspecified"))
    )
    (net (code "22") (name "Net-(C9-Pad1)") (class "Default")
      (node (ref "C9") (pin "1") (pinfunction "1_1") (pintype "input"))
      (node (ref "R9") (pin "2") (pinfunction "2_2") (pintype "unspecified"))
    )
    (net (code "23") (name "Net-(C10-Pad1)") (class "Default")
      (node (ref "C10") (pin "1") (pinfunction "1_1") (pintype "input"))
      (node (ref "R10") (pin "2") (pinfunction "2_2") (pintype "unspecified"))
    )
    (net (code "24") (name "Net-(D1-A)") (class "Default")
      (node (ref "D1") (pin "2") (pinfunction "A_2") (pintype "unspecified"))
      (node (ref "SW1") (pin "2") (pinfunction "2_2") (pintype "unspecified"))
    )
    (net (code "25") (name "Net-(D2-A)") (class "Default")
      (node (ref "D2") (pin "2") (pinfunction "A_2") (pintype "unspecified"))
      (node (ref "SW2") (pin "2") (pinfunction "2_2") (pintype "unspecified"))
    )
    (net (code "26") (name "Net-(D3-A)") (class "Default")
      (node (ref "D3") (pin "2") (pinfunction "A_2") (pintype "unspecified"))
      (node (ref "SW3") (pin "2") (pinfunction "2_2") (pintype "unspecified"))
    )
    (net (code "27") (name "Net-(D4-A)") (class "Default")
      (node (ref "D4") (pin "2") (pinfunction "A_2") (pintype "unspecified"))
      (node (ref "SW4") (pin "2") (pinfunction "2_2") (pintype "unspecified"))
    )
    (net (code "28") (name "Net-(D5-A)") (class "Default")
      (node (ref "D5") (pin "2") (pinfunction "A_2") (pintype "unspecified"))
      (node (ref "SW5") (pin "2") (pinfunction "2_2") (pintype "unspecified"))
    )
    (net (code "29") (name "Net-(D6-A)") (class "Default")
      (node (ref "D6") (pin "2") (pinfunction "A_2") (pintype "unspecified"))
      (node (ref "SW6") (pin "2") (pinfunction "2_2") (pintype "unspecified"))
    )
    (net (code "30") (name "Net-(D7-A)") (class "Default")
      (node (ref "D7") (pin "2") (pinfunction "A_2") (pintype "unspecified"))
      (node (ref "SW7") (pin "2") (pinfunction "2_2") (pintype "unspecified"))
    )
    (net (code "31") (name "Net-(D8-A)") (class "Default")
      (node (ref "D8") (pin "2") (pinfunction "A_2") (pintype "unspecified"))
      (node (ref "SW8") (pin "2") (pinfunction "2_2") (pintype "unspecified"))
    )
    (net (code "32") (name "Net-(D9-A)") (class "Default")
      (node (ref "D9") (pin "2") (pinfunction "A_2") (pintype "unspecified"))
      (node (ref "SW9") (pin "2") (pinfunction "2_2") (pintype "unspecified"))
    )
    (net (code "33") (name "Net-(D10-A)") (class "Default")
      (node (ref "D10") (pin "2") (pinfunction "A_2") (pintype "unspecified"))
      (node (ref "SW10") (pin "2") (pinfunction "2_2") (pintype "unspecified"))
    )
    (net (code "34") (name "Net-(D11-A)") (class "Default")
      (node (ref "D11") (pin "2") (pinfunction "A_2") (pintype "unspecified"))
      (node (ref "SW11") (pin "2") (pinfunction "2_2") (pintype "unspecified"))
    )
    (net (code "35") (name "Net-(D12-A)") (class "Default")
      (node (ref "D12") (pin "2") (pinfunction "A_2") (pintype "unspecified"))
      (node (ref "SW12") (pin "2") (pinfunction "2_2") (pintype "unspecified"))
    )
    (net (code "36") (name "Net-(D13-A)") (class "Default")
      (node (ref "D13") (pin "2") (pinfunction "A_2") (pintype "unspecified"))
      (node (ref "SW13") (pin "2") (pinfunction "2_2") (pintype "unspecified"))
    )
    (net (code "37") (name "Net-(D14-A)") (class "Default")
      (node (ref "D14") (pin "2") (pinfunction "A_2") (pintype "unspecified"))
      (node (ref "SW14") (pin "2") (pinfunction "2_2") (pintype "unspecified"))
    )
    (net (code "38") (name "Net-(D15-A)") (class "Default")
      (node (ref "D15") (pin "2") (pinfunction "A_2") (pintype "unspecified"))
      (node (ref "SW15") (pin "2") (pinfunction "2_2") (pintype "unspecified"))
    )
    (net (code "39") (name "Net-(D16-A)") (class "Default")
      (node (ref "D16") (pin "2") (pinfunction "A_2") (pintype "unspecified"))
      (node (ref "SW16") (pin "2") (pinfunction "2_2") (pintype "unspecified"))
    )
    (net (code "40") (name "Net-(D17-A)") (class "Default")
      (node (ref "D17") (pin "2") (pinfunction "A_2") (pintype "unspecified"))
      (node (ref "SW17") (pin "2") (pinfunction "2_2") (pintype "unspecified"))
    )
    (net (code "41") (name "Net-(D18-A)") (class "Default")
      (node (ref "D18") (pin "2") (pinfunction "A_2") (pintype "unspecified"))
      (node (ref "SW18") (pin "2") (pinfunction "2_2") (pintype "unspecified"))
    )
    (net (code "42") (name "Net-(D19-A)") (class "Default")
      (node (ref "D19") (pin "2") (pinfunction "A_2") (pintype "unspecified"))
      (node (ref "SW19") (pin "2") (pinfunction "2_2") (pintype "unspecified"))
    )
    (net (code "43") (name "Net-(D20-A)") (class "Default")
      (node (ref "D20") (pin "2") (pinfunction "A_2") (pintype "unspecified"))
      (node (ref "SW20") (pin "2") (pinfunction "2_2") (pintype "unspecified"))
    )
    (net (code "44") (name "Net-(D21-A)") (class "Default")
      (node (ref "D21") (pin "2") (pinfunction "A_2") (pintype "unspecified"))
      (node (ref "SW21") (pin "2") (pinfunction "2_2") (pintype "unspecified"))
    )
    (net (code "45") (name "Net-(D22-A)") (class "Default")
      (node (ref "D22") (pin "2") (pinfunction "A_2") (pintype "unspecified"))
      (node (ref "SW22") (pin "2") (pinfunction "2_2") (pintype "unspecified"))
    )
    (net (code "46") (name "Net-(D23-A)") (class "Default")
      (node (ref "D23") (pin "2") (pinfunction "A_2") (pintype "unspecified"))
      (node (ref "SW23") (pin "2") (pinfunction "2_2") (pintype "unspecified"))
    )
    (net (code "47") (name "Net-(D24-A)") (class "Default")
      (node (ref "D24") (pin "2") (pinfunction "A_2") (pintype "unspecified"))
      (node (ref "SW24") (pin "2") (pinfunction "2_2") (pintype "unspecified"))
    )
    (net (code "48") (name "Net-(D25-A)") (class "Default")
      (node (ref "D25") (pin "2") (pinfunction "A_2") (pintype "unspecified"))
      (node (ref "SW25") (pin "2") (pinfunction "2_2") (pintype "unspecified"))
    )
    (net (code "49") (name "Net-(D26-A)") (class "Default")
      (node (ref "D26") (pin "2") (pinfunction "A_2") (pintype "unspecified"))
      (node (ref "SW26") (pin "2") (pinfunction "2_2") (pintype "unspecified"))
    )
    (net (code "50") (name "Net-(D27-A)") (class "Default")
      (node (ref "D27") (pin "2") (pinfunction "A_2") (pintype "unspecified"))
      (node (ref "SW27") (pin "2") (pinfunction "2_2") (pintype "unspecified"))
    )
    (net (code "51") (name "Net-(D28-A)") (class "Default")
      (node (ref "D28") (pin "2") (pinfunction "A_2") (pintype "unspecified"))
      (node (ref "SW28") (pin "2") (pinfunction "2_2") (pintype "unspecified"))
    )
    (net (code "52") (name "Net-(D29-A)") (class "Default")
      (node (ref "D29") (pin "2") (pinfunction "A_2") (pintype "unspecified"))
      (node (ref "SW29") (pin "2") (pinfunction "2_2") (pintype "unspecified"))
    )
    (net (code "53") (name "Net-(D30-A)") (class "Default")
      (node (ref "D30") (pin "2") (pinfunction "A_2") (pintype "unspecified"))
      (node (ref "SW30") (pin "2") (pinfunction "2_2") (pintype "unspecified"))
    )
    (net (code "54") (name "Net-(D31-A)") (class "Default")
      (node (ref "D31") (pin "2") (pinfunction "A_2") (pintype "unspecified"))
      (node (ref "SW31") (pin "2") (pinfunction "2_2") (pintype "unspecified"))
    )
    (net (code "55") (name "Net-(D32-A)") (class "Default")
      (node (ref "D32") (pin "2") (pinfunction "A_2") (pintype "unspecified"))
      (node (ref "SW32") (pin "2") (pinfunction "2_2") (pintype "unspecified"))
    )
    (net (code "56") (name "Net-(R1-Pad3)") (class "Default")
      (node (ref "R1") (pin "3") (pinfunction "3_3") (pintype "unspecified"))
      (node (ref "R10") (pin "3") (pinfunction "3_3") (pintype "unspecified"))
      (node (ref "R2") (pin "3") (pinfunction "3_3") (pintype "unspecified"))
      (node (ref "R3") (pin "3") (pinfunction "3_3") (pintype "unspecified"))
      (node (ref "R4") (pin "3") (pinfunction "3_3") (pintype "unspecified"))
      (node (ref "R5") (pin "3") (pinfunction "3_3") (pintype "unspecified"))
      (node (ref "R6") (pin "3") (pinfunction "3_3") (pintype "unspecified"))
      (node (ref "R7") (pin "3") (pinfunction "3_3") (pintype "unspecified"))
      (node (ref "R8") (pin "3") (pinfunction "3_3") (pintype "unspecified"))
      (node (ref "R9") (pin "3") (pinfunction "3_3") (pintype "unspecified"))
      (node (ref "U1") (pin "27") (pinfunction "3V3_27") (pintype "input"))
    )
    (net (code "57") (name "Net-(U1-16(A2)-SCL1-RX4)") (class "Default")
      (node (ref "C3") (pin "2") (pinfunction "2_2") (pintype "input"))
      (node (ref "U1") (pin "35") (pinfunction "16(A2)-SCL1-RX4_35") (pintype "input"))
    )
    (net (code "58") (name "Net-(U1-17(A3)-SDA1-TX4)") (class "Default")
      (node (ref "C4") (pin "2") (pinfunction "2_2") (pintype "input"))
      (node (ref "U1") (pin "34") (pinfunction "17(A3)-SDA1-TX4_34") (pintype "input"))
    )
    (net (code "59") (name "Net-(U1-18(A4)-SDA)") (class "Default")
      (node (ref "C5") (pin "2") (pinfunction "2_2") (pintype "input"))
      (node (ref "U1") (pin "33") (pinfunction "18(A4)-SDA_33") (pintype "input"))
    )
    (net (code "60") (name "Net-(U1-19(A5)-SCL)") (class "Default")
      (node (ref "C6") (pin "1") (pinfunction "1_1") (pintype "input"))
      (node (ref "U1") (pin "32") (pinfunction "19(A5)-SCL_32") (pintype "input"))
    )
    (net (code "61") (name "Net-(U1-20(A6)-TX5)") (class "Default")
      (node (ref "C7") (pin "2") (pinfunction "2_2") (pintype "input"))
      (node (ref "U1") (pin "31") (pinfunction "20(A6)-TX5_31") (pintype "input"))
    )
    (net (code "62") (name "Net-(U1-21(A7)-RX5)") (class "Default")
      (node (ref "C8") (pin "2") (pinfunction "2_2") (pintype "input"))
      (node (ref "U1") (pin "30") (pinfunction "21(A7)-RX5_30") (pintype "input"))
    )
    (net (code "63") (name "Net-(U1-22(A8))") (class "Default")
      (node (ref "C9") (pin "2") (pinfunction "2_2") (pintype "input"))
      (node (ref "U1") (pin "29") (pinfunction "22(A8)_29") (pintype "input"))
    )
    (net (code "64") (name "Net-(U1-23(A9))") (class "Default")
      (node (ref "C10") (pin "2") (pinfunction "2_2") (pintype "input"))
      (node (ref "U1") (pin "28") (pinfunction "23(A9)_28") (pintype "input"))
    )
    (net (code "65") (name "Net-(U1-38(A14))") (class "Default")
      (node (ref "C1") (pin "2") (pinfunction "2_2") (pintype "input"))
      (node (ref "U1") (pin "43") (pinfunction "38(A14)_43") (pintype "input"))
    )
    (net (code "66") (name "Net-(U1-39(A15))") (class "Default")
      (node (ref "C2") (pin "2") (pinfunction "2_2") (pintype "input"))
      (node (ref "U1") (pin "42") (pinfunction "39(A15)_42") (pintype "input"))
    )
    (net (code "67") (name "unconnected-(R1-Pad4)") (class "Default")
      (node (ref "R1") (pin "4") (pinfunction "4_4") (pintype "unspecified"))
    )
    (net (code "68") (name "unconnected-(R1-Pad5)") (class "Default")
      (node (ref "R1") (pin "5") (pinfunction "5_5") (pintype "unspecified"))
    )
    (net (code "69") (name "unconnected-(R1-Pad6)") (class "Default")
      (node (ref "R1") (pin "6") (pinfunction "6_6") (pintype "unspecified"))
    )
    (net (code "70") (name "unconnected-(R1-Pad7)") (class "Default")
      (node (ref "R1") (pin "7") (pinfunction "7_7") (pintype "unspecified"))
    )
    (net (code "71") (name "unconnected-(R2-Pad4)") (class "Default")
      (node (ref "R2") (pin "4") (pinfunction "4_4") (pintype "unspecified"))
    )
    (net (code "72") (name "unconnected-(R2-Pad5)") (class "Default")
      (node (ref "R2") (pin "5") (pinfunction "5_5") (pintype "unspecified"))
    )
    (net (code "73") (name "unconnected-(R2-Pad6)") (class "Default")
      (node (ref "R2") (pin "6") (pinfunction "6_6") (pintype "unspecified"))
    )
    (net (code "74") (name "unconnected-(R2-Pad7)") (class "Default")
      (node (ref "R2") (pin "7") (pinfunction "7_7") (pintype "unspecified"))
    )
    (net (code "75") (name "unconnected-(R3-Pad4)") (class "Default")
      (node (ref "R3") (pin "4") (pinfunction "4_4") (pintype "unspecified"))
    )
    (net (code "76") (name "unconnected-(R3-Pad5)") (class "Default")
      (node (ref "R3") (pin "5") (pinfunction "5_5") (pintype "unspecified"))
    )
    (net (code "77") (name "unconnected-(R3-Pad6)") (class "Default")
      (node (ref "R3") (pin "6") (pinfunction "6_6") (pintype "unspecified"))
    )
    (net (code "78") (name "unconnected-(R3-Pad7)") (class "Default")
      (node (ref "R3") (pin "7") (pinfunction "7_7") (pintype "unspecified"))
    )
    (net (code "79") (name "unconnected-(R4-Pad4)") (class "Default")
      (node (ref "R4") (pin "4") (pinfunction "4_4") (pintype "unspecified"))
    )
    (net (code "80") (name "unconnected-(R4-Pad5)") (class "Default")
      (node (ref "R4") (pin "5") (pinfunction "5_5") (pintype "unspecified"))
    )
    (net (code "81") (name "unconnected-(R4-Pad6)") (class "Default")
      (node (ref "R4") (pin "6") (pinfunction "6_6") (pintype "unspecified"))
    )
    (net (code "82") (name "unconnected-(R4-Pad7)") (class "Default")
      (node (ref "R4") (pin "7") (pinfunction "7_7") (pintype "unspecified"))
    )
    (net (code "83") (name "unconnected-(R5-Pad4)") (class "Default")
      (node (ref "R5") (pin "4") (pinfunction "4_4") (pintype "unspecified"))
    )
    (net (code "84") (name "unconnected-(R5-Pad5)") (class "Default")
      (node (ref "R5") (pin "5") (pinfunction "5_5") (pintype "unspecified"))
    )
    (net (code "85") (name "unconnected-(R5-Pad6)") (class "Default")
      (node (ref "R5") (pin "6") (pinfunction "6_6") (pintype "unspecified"))
    )
    (net (code "86") (name "unconnected-(R5-Pad7)") (class "Default")
      (node (ref "R5") (pin "7") (pinfunction "7_7") (pintype "unspecified"))
    )
    (net (code "87") (name "unconnected-(R6-Pad4)") (class "Default")
      (node (ref "R6") (pin "4") (pinfunction "4_4") (pintype "unspecified"))
    )
    (net (code "88") (name "unconnected-(R6-Pad5)") (class "Default")
      (node (ref "R6") (pin "5") (pinfunction "5_5") (pintype "unspecified"))
    )
    (net (code "89") (name "unconnected-(R6-Pad6)") (class "Default")
      (node (ref "R6") (pin "6") (pinfunction "6_6") (pintype "unspecified"))
    )
    (net (code "90") (name "unconnected-(R6-Pad7)") (class "Default")
      (node (ref "R6") (pin "7") (pinfunction "7_7") (pintype "unspecified"))
    )
    (net (code "91") (name "unconnected-(R7-Pad4)") (class "Default")
      (node (ref "R7") (pin "4") (pinfunction "4_4") (pintype "unspecified"))
    )
    (net (code "92") (name "unconnected-(R7-Pad5)") (class "Default")
      (node (ref "R7") (pin "5") (pinfunction "5_5") (pintype "unspecified"))
    )
    (net (code "93") (name "unconnected-(R7-Pad6)") (class "Default")
      (node (ref "R7") (pin "6") (pinfunction "6_6") (pintype "unspecified"))
    )
    (net (code "94") (name "unconnected-(R7-Pad7)") (class "Default")
      (node (ref "R7") (pin "7") (pinfunction "7_7") (pintype "unspecified"))
    )
    (net (code "95") (name "unconnected-(R8-Pad4)") (class "Default")
      (node (ref "R8") (pin "4") (pinfunction "4_4") (pintype "unspecified"))
    )
    (net (code "96") (name "unconnected-(R8-Pad5)") (class "Default")
      (node (ref "R8") (pin "5") (pinfunction "5_5") (pintype "unspecified"))
    )
    (net (code "97") (name "unconnected-(R8-Pad6)") (class "Default")
      (node (ref "R8") (pin "6") (pinfunction "6_6") (pintype "unspecified"))
    )
    (net (code "98") (name "unconnected-(R8-Pad7)") (class "Default")
      (node (ref "R8") (pin "7") (pinfunction "7_7") (pintype "unspecified"))
    )
    (net (code "99") (name "unconnected-(R9-Pad4)") (class "Default")
      (node (ref "R9") (pin "4") (pinfunction "4_4") (pintype "unspecified"))
    )
    (net (code "100") (name "unconnected-(R9-Pad5)") (class "Default")
      (node (ref "R9") (pin "5") (pinfunction "5_5") (pintype "unspecified"))
    )
    (net (code "101") (name "unconnected-(R9-Pad6)") (class "Default")
      (node (ref "R9") (pin "6") (pinfunction "6_6") (pintype "unspecified"))
    )
    (net (code "102") (name "unconnected-(R9-Pad7)") (class "Default")
      (node (ref "R9") (pin "7") (pinfunction "7_7") (pintype "unspecified"))
    )
    (net (code "103") (name "unconnected-(R10-Pad4)") (class "Default")
      (node (ref "R10") (pin "4") (pinfunction "4_4") (pintype "unspecified"))
    )
    (net (code "104") (name "unconnected-(R10-Pad5)") (class "Default")
      (node (ref "R10") (pin "5") (pinfunction "5_5") (pintype "unspecified"))
    )
    (net (code "105") (name "unconnected-(R10-Pad6)") (class "Default")
      (node (ref "R10") (pin "6") (pinfunction "6_6") (pintype "unspecified"))
    )
    (net (code "106") (name "unconnected-(R10-Pad7)") (class "Default")
      (node (ref "R10") (pin "7") (pinfunction "7_7") (pintype "unspecified"))
    )
    (net (code "107") (name "unconnected-(U1-3V3-Pad15)") (class "Default")
      (node (ref "U1") (pin "15") (pinfunction "3V3_15") (pintype "input"))
    )
    (net (code "108") (name "unconnected-(U1-6-Pad8)") (class "Default")
      (node (ref "U1") (pin "8") (pinfunction "6_8") (pintype "input"))
    )
    (net (code "109") (name "unconnected-(U1-10-Pad12)") (class "Default")
      (node (ref "U1") (pin "12") (pinfunction "10_12") (pintype "input"))
    )
    (net (code "110") (name "unconnected-(U1-11-MOSI-Pad13)") (class "Default")
      (node (ref "U1") (pin "13") (pinfunction "11-MOSI_13") (pintype "input"))
    )
    (net (code "111") (name "unconnected-(U1-12-MISO-Pad14)") (class "Default")
      (node (ref "U1") (pin "14") (pinfunction "12-MISO_14") (pintype "input"))
    )
    (net (code "112") (name "unconnected-(U1-13-SCK-Pad38)") (class "Default")
      (node (ref "U1") (pin "38") (pinfunction "13-SCK_38") (pintype "input"))
    )
    (net (code "113") (name "unconnected-(U1-14(A0)-TX3-Pad37)") (class "Default")
      (node (ref "U1") (pin "37") (pinfunction "14(A0)-TX3_37") (pintype "input"))
    )
    (net (code "114") (name "unconnected-(U1-15(A1)-RX3-Pad36)") (class "Default")
      (node (ref "U1") (pin "36") (pinfunction "15(A1)-RX3_36") (pintype "input"))
    )
    (net (code "115") (name "unconnected-(U1-24(A10)-SCL2-TX6-Pad16)") (class "Default")
      (node (ref "U1") (pin "16") (pinfunction "24(A10)-SCL2-TX6_16") (pintype "input"))
    )
    (net (code "116") (name "unconnected-(U1-25(A11)-SDA2-RX6-Pad17)") (class "Default")
      (node (ref "U1") (pin "17") (pinfunction "25(A11)-SDA2-RX6_17") (pintype "input"))
    )
    (net (code "117") (name "unconnected-(U1-26(A12)-MOSI1-Pad18)") (class "Default")
      (node (ref "U1") (pin "18") (pinfunction "26(A12)-MOSI1_18") (pintype "input"))
    )
    (net (code "118") (name "unconnected-(U1-27(A13)-SCK1-Pad19)") (class "Default")
      (node (ref "U1") (pin "19") (pinfunction "27(A13)-SCK1_19") (pintype "input"))
    )
    (net (code "119") (name "unconnected-(U1-28-RX7-Pad20)") (class "Default")
      (node (ref "U1") (pin "20") (pinfunction "28-RX7_20") (pintype "input"))
    )
    (net (code "120") (name "unconnected-(U1-29-TX7-Pad21)") (class "Default")
      (node (ref "U1") (pin "21") (pinfunction "29-TX7_21") (pintype "input"))
    )
    (net (code "121") (name "unconnected-(U1-33-Pad48)") (class "Default")
      (node (ref "U1") (pin "48") (pinfunction "33_48") (pintype "input"))
    )
    (net (code "122") (name "unconnected-(U1-34-RX8-Pad47)") (class "Default")
      (node (ref "U1") (pin "47") (pinfunction "34-RX8_47") (pintype "input"))
    )
    (net (code "123") (name "unconnected-(U1-35-TX8-Pad46)") (class "Default")
      (node (ref "U1") (pin "46") (pinfunction "35-TX8_46") (pintype "input"))
    )
    (net (code "124") (name "unconnected-(U1-36-Pad45)") (class "Default")
      (node (ref "U1") (pin "45") (pinfunction "36_45") (pintype "input"))
    )
    (net (code "125") (name "unconnected-(U1-37-Pad44)") (class "Default")
      (node (ref "U1") (pin "44") (pinfunction "37_44") (pintype "input"))
    )
    (net (code "126") (name "unconnected-(U1-40(A16)-Pad41)") (class "Default")
      (node (ref "U1") (pin "41") (pinfunction "40(A16)_41") (pintype "input"))
    )
    (net (code "127") (name "unconnected-(U1-41(A17)-Pad40)") (class "Default")
      (node (ref "U1") (pin "40") (pinfunction "41(A17)_40") (pintype "input"))
    )
    (net (code "128") (name "unconnected-(U1-VIN-Pad25)") (class "Default")
      (node (ref "U1") (pin "25") (pinfunction "VIN_25") (pintype "input"))
    )
  )
)
